# Ethernet.net
KiCad netlist of a schematic drawn in Altium Designer
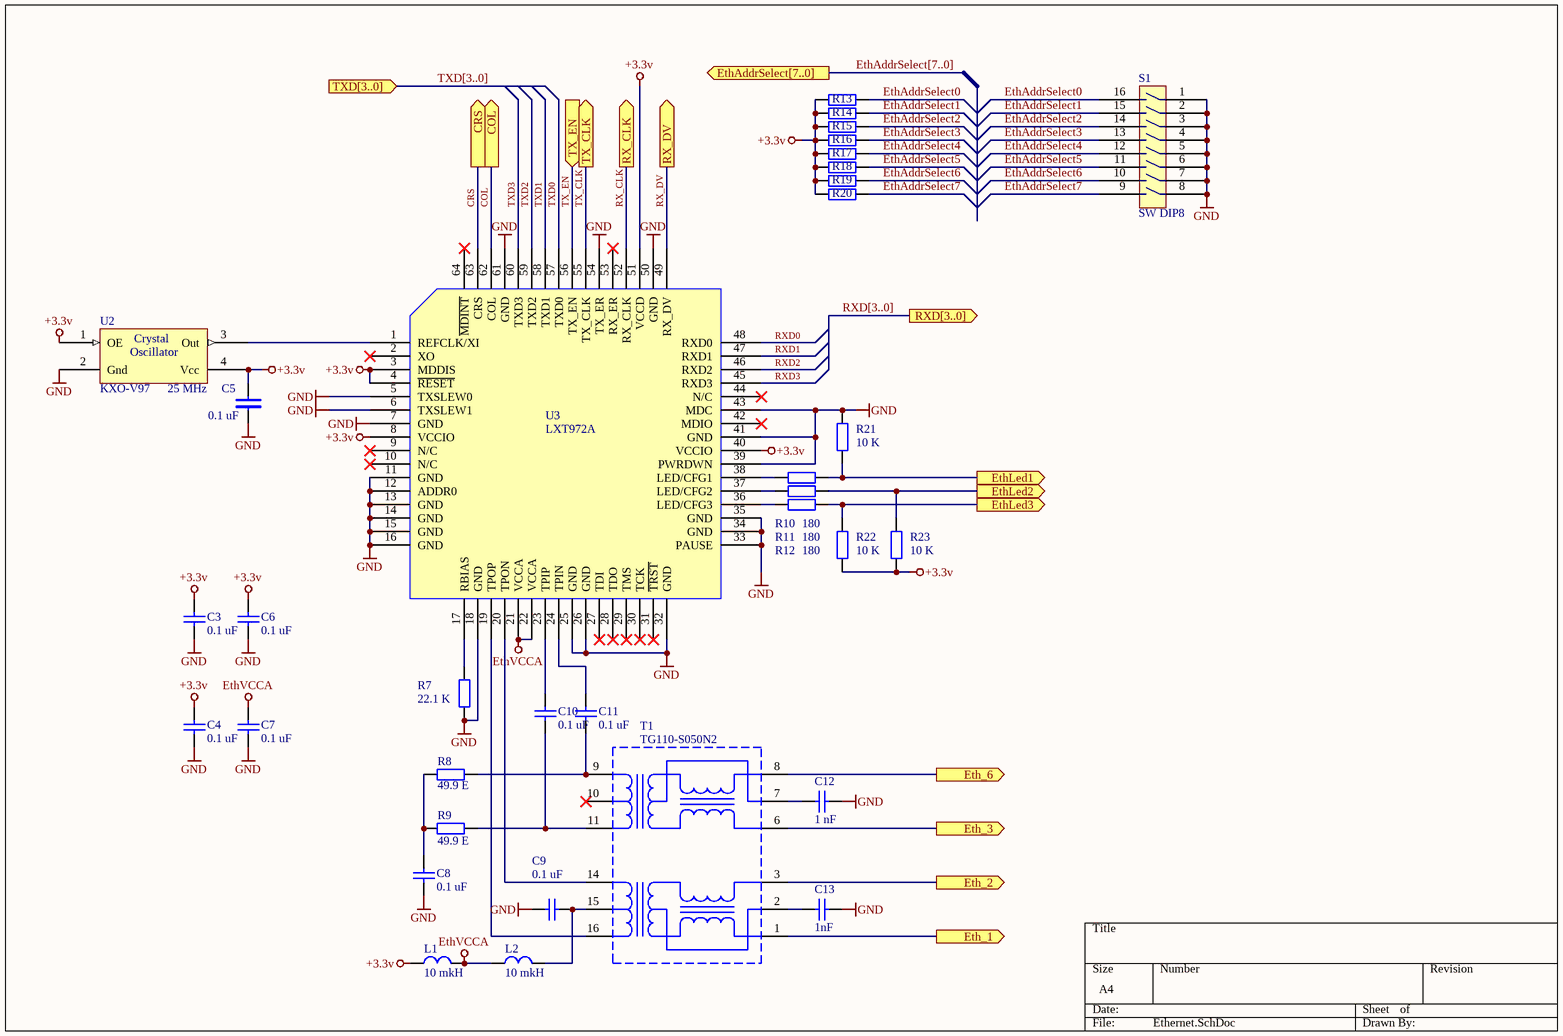
[diagram p0: Ethernet.SchDoc]

(export (version "E")
  (design (tool "Eeschema 10.0.6"))
  (components
    (comp (ref "C3")
      (value "0.1 uF")
      (footprint "0603")
      (description "Capacitor")
      (fields (field (name "PUBLISHER") "Altium Limited"))
      (libsource (lib "pcblib1") (part "Cap"))
    )
    (comp (ref "C4")
      (value "0.1 uF")
      (footprint "0603")
      (description "Capacitor")
      (fields (field (name "PUBLISHER") "Altium Limited"))
      (libsource (lib "pcblib1") (part "Cap"))
    )
    (comp (ref "C5") (value "0.1 uF") (footprint "1206") (libsource (lib "*") (part "C")))
    (comp (ref "C6")
      (value "0.1 uF")
      (footprint "0603")
      (description "Capacitor")
      (fields (field (name "PUBLISHER") "Altium Limited"))
      (libsource (lib "pcblib1") (part "Cap"))
    )
    (comp (ref "C7")
      (value "0.1 uF")
      (footprint "0603")
      (description "Capacitor")
      (fields (field (name "PUBLISHER") "Altium Limited"))
      (libsource (lib "pcblib1") (part "Cap"))
    )
    (comp (ref "C8")
      (value "0.1 uF")
      (footprint "0603")
      (description "Capacitor")
      (fields (field (name "PUBLISHER") "Altium Limited"))
      (libsource (lib "pcblib1") (part "Cap"))
    )
    (comp (ref "C9")
      (value "0.1 uF")
      (footprint "0603")
      (description "Capacitor")
      (fields (field (name "PUBLISHER") "Altium Limited"))
      (libsource (lib "pcblib1") (part "Cap"))
    )
    (comp (ref "C10")
      (value "0.1 uF")
      (footprint "0603")
      (description "Capacitor")
      (fields (field (name "PUBLISHER") "Altium Limited"))
      (libsource (lib "pcblib1") (part "Cap"))
    )
    (comp (ref "C11")
      (value "0.1 uF")
      (footprint "0603")
      (description "Capacitor")
      (fields (field (name "PUBLISHER") "Altium Limited"))
      (libsource (lib "pcblib1") (part "Cap"))
    )
    (comp (ref "C12")
      (value "1 nF")
      (footprint "1206")
      (description "Capacitor")
      (fields (field (name "PUBLISHER") "Altium Limited"))
      (libsource (lib "pcblib1") (part "Cap"))
    )
    (comp (ref "C13")
      (value "1nF")
      (footprint "1206")
      (description "Capacitor")
      (fields (field (name "Comment") "1 nF") (field (name "PUBLISHER") "Altium Limited"))
      (libsource (lib "pcblib1") (part "Cap"))
    )
    (comp (ref "L1")
      (value "10 mkH")
      (footprint "0805")
      (description "Inductor")
      (fields (field (name "PUBLISHER") "Altium Limited"))
      (libsource (lib "pcblib1") (part "Inductor"))
    )
    (comp (ref "L2")
      (value "10 mkH")
      (footprint "0805")
      (description "Inductor")
      (fields (field (name "PUBLISHER") "Altium Limited"))
      (libsource (lib "pcblib1") (part "Inductor"))
    )
    (comp (ref "R7")
      (value "22.1 K")
      (footprint "0805")
      (description "Resistor")
      (fields (field (name "PUBLISHER") "Altium Limited"))
      (libsource (lib "") (part "Res2_3"))
    )
    (comp (ref "R8")
      (value "49.9 E")
      (footprint "0805")
      (description "Resistor")
      (fields (field (name "PUBLISHER") "Altium Limited"))
      (libsource (lib "") (part "Res2_1"))
    )
    (comp (ref "R9")
      (value "49.9 E")
      (footprint "0805")
      (description "Resistor")
      (fields (field (name "PUBLISHER") "Altium Limited"))
      (libsource (lib "OD3M") (part "Res2"))
    )
    (comp (ref "R10")
      (value "180")
      (footprint "0805")
      (description "Resistor")
      (fields (field (name "PUBLISHER") "Altium Limited"))
      (libsource (lib "") (part "Res2_1"))
    )
    (comp (ref "R11")
      (value "180")
      (footprint "0805")
      (description "Resistor")
      (fields (field (name "PUBLISHER") "Altium Limited"))
      (libsource (lib "") (part "Res2_1"))
    )
    (comp (ref "R12")
      (value "180")
      (footprint "0805")
      (description "Resistor")
      (fields (field (name "PUBLISHER") "Altium Limited"))
      (libsource (lib "") (part "Res2_1"))
    )
    (comp (ref "R13")
      (value "10 K")
      (footprint "0603")
      (description "Resistor")
      (fields (field (name "PUBLISHER") "Altium Limited"))
      (libsource (lib "OD3M") (part "Res2"))
    )
    (comp (ref "R14")
      (value "10 K")
      (footprint "0603")
      (description "Resistor")
      (fields (field (name "PUBLISHER") "Altium Limited"))
      (libsource (lib "OD3M") (part "Res2"))
    )
    (comp (ref "R15")
      (value "10 K")
      (footprint "0603")
      (description "Resistor")
      (fields (field (name "PUBLISHER") "Altium Limited"))
      (libsource (lib "OD3M") (part "Res2"))
    )
    (comp (ref "R16")
      (value "10 K")
      (footprint "0603")
      (description "Resistor")
      (fields (field (name "PUBLISHER") "Altium Limited"))
      (libsource (lib "OD3M") (part "Res2"))
    )
    (comp (ref "R17")
      (value "10 K")
      (footprint "0603")
      (description "Resistor")
      (fields (field (name "PUBLISHER") "Altium Limited"))
      (libsource (lib "OD3M") (part "Res2"))
    )
    (comp (ref "R18")
      (value "10 K")
      (footprint "0603")
      (description "Resistor")
      (fields (field (name "PUBLISHER") "Altium Limited"))
      (libsource (lib "OD3M") (part "Res2"))
    )
    (comp (ref "R19")
      (value "10 K")
      (footprint "0603")
      (description "Resistor")
      (fields (field (name "PUBLISHER") "Altium Limited"))
      (libsource (lib "OD3M") (part "Res2"))
    )
    (comp (ref "R20")
      (value "10 K")
      (footprint "0603")
      (description "Resistor")
      (fields (field (name "PUBLISHER") "Altium Limited"))
      (libsource (lib "OD3M") (part "Res2"))
    )
    (comp (ref "R21")
      (value "10 K")
      (footprint "0603")
      (description "Resistor")
      (fields (field (name "PUBLISHER") "Altium Limited"))
      (libsource (lib "") (part "Res2_2"))
    )
    (comp (ref "R22")
      (value "10 K")
      (footprint "0603")
      (description "Resistor")
      (fields (field (name "PUBLISHER") "Altium Limited"))
      (libsource (lib "") (part "Res2_2"))
    )
    (comp (ref "R23")
      (value "10 K")
      (footprint "0603")
      (description "Resistor")
      (fields (field (name "PUBLISHER") "Altium Limited"))
      (libsource (lib "") (part "Res2_2"))
    )
    (comp (ref "S1") (value "SW DIP8") (footprint "SWD1-8") (libsource (lib "Adevice") (part "SW DIP8")))
    (comp (ref "T1")
      (value "TG110-S050N2")
      (footprint "SO-G16/G6.9")
      (libsource (lib "Schlib1") (part "TG110-S050N2"))
    )
    (comp (ref "U2")
      (value "KXO-V97")
      (footprint "KXO-97")
      (description "Crystal Oscillator (SMD)")
      (libsource (lib "Mylib") (part "SG-636"))
    )
    (comp (ref "U3")
      (value "LXT972A")
      (footprint "TQFP64")
      (libsource (lib "MyIntegratedLibrary") (part "LXT972A"))
    )
  )
  (nets
    (net (code "1") (name "+3.3v") (class "Default")
      (node (ref "C3") (pin "2") (pinfunction "2_2") (pintype "passive"))
      (node (ref "C4") (pin "2") (pinfunction "2_2") (pintype "passive"))
      (node (ref "C5") (pin "2") (pinfunction "2_2") (pintype "passive"))
      (node (ref "C6") (pin "2") (pinfunction "2_2") (pintype "passive"))
      (node (ref "L1") (pin "1") (pinfunction "1_1") (pintype "passive"))
      (node (ref "R13") (pin "2") (pinfunction "2_2") (pintype "passive"))
      (node (ref "R14") (pin "2") (pinfunction "2_2") (pintype "passive"))
      (node (ref "R15") (pin "2") (pinfunction "2_2") (pintype "passive"))
      (node (ref "R16") (pin "2") (pinfunction "2_2") (pintype "passive"))
      (node (ref "R17") (pin "2") (pinfunction "2_2") (pintype "passive"))
      (node (ref "R18") (pin "2") (pinfunction "2_2") (pintype "passive"))
      (node (ref "R19") (pin "2") (pinfunction "2_2") (pintype "passive"))
      (node (ref "R20") (pin "2") (pinfunction "2_2") (pintype "passive"))
      (node (ref "R22") (pin "1") (pinfunction "1_1") (pintype "passive"))
      (node (ref "R23") (pin "1") (pinfunction "1_1") (pintype "passive"))
      (node (ref "U2") (pin "1") (pinfunction "OE_1") (pintype "input"))
      (node (ref "U2") (pin "4") (pinfunction "Vcc_4") (pintype "passive"))
      (node (ref "U3") (pin "3") (pinfunction "MDDIS_3") (pintype "passive"))
      (node (ref "U3") (pin "4") (pinfunction "RESET_4") (pintype "passive"))
      (node (ref "U3") (pin "40") (pinfunction "VCCIO_40") (pintype "passive"))
      (node (ref "U3") (pin "51") (pinfunction "VCCD_51") (pintype "passive"))
      (node (ref "U3") (pin "8") (pinfunction "VCCIO_8") (pintype "passive"))
    )
    (net (code "2") (name "/COL") (class "Default")
      (node (ref "U3") (pin "62") (pinfunction "COL_62") (pintype "passive"))
    )
    (net (code "3") (name "/CRS") (class "Default")
      (node (ref "U3") (pin "63") (pinfunction "CRS_63") (pintype "passive"))
    )
    (net (code "4") (name "/EthAddrSelect0") (class "Default")
      (node (ref "R13") (pin "1") (pinfunction "1_1") (pintype "passive"))
      (node (ref "S1") (pin "16") (pinfunction "16_16") (pintype "passive"))
    )
    (net (code "5") (name "/EthAddrSelect1") (class "Default")
      (node (ref "R14") (pin "1") (pinfunction "1_1") (pintype "passive"))
      (node (ref "S1") (pin "15") (pinfunction "15_15") (pintype "passive"))
    )
    (net (code "6") (name "/EthAddrSelect2") (class "Default")
      (node (ref "R15") (pin "1") (pinfunction "1_1") (pintype "passive"))
      (node (ref "S1") (pin "14") (pinfunction "14_14") (pintype "passive"))
    )
    (net (code "7") (name "/EthAddrSelect3") (class "Default")
      (node (ref "R16") (pin "1") (pinfunction "1_1") (pintype "passive"))
      (node (ref "S1") (pin "13") (pinfunction "13_13") (pintype "passive"))
    )
    (net (code "8") (name "/EthAddrSelect4") (class "Default")
      (node (ref "R17") (pin "1") (pinfunction "1_1") (pintype "passive"))
      (node (ref "S1") (pin "12") (pinfunction "12_12") (pintype "passive"))
    )
    (net (code "9") (name "/EthAddrSelect5") (class "Default")
      (node (ref "R18") (pin "1") (pinfunction "1_1") (pintype "passive"))
      (node (ref "S1") (pin "11") (pinfunction "11_11") (pintype "passive"))
    )
    (net (code "10") (name "/EthAddrSelect6") (class "Default")
      (node (ref "R19") (pin "1") (pinfunction "1_1") (pintype "passive"))
      (node (ref "S1") (pin "10") (pinfunction "10_10") (pintype "passive"))
    )
    (net (code "11") (name "/EthAddrSelect7") (class "Default")
      (node (ref "R20") (pin "1") (pinfunction "1_1") (pintype "passive"))
      (node (ref "S1") (pin "9") (pinfunction "9_9") (pintype "passive"))
    )
    (net (code "13") (name "/EthLed1") (class "Default")
      (node (ref "R10") (pin "2") (pinfunction "2_2") (pintype "passive"))
      (node (ref "R21") (pin "1") (pinfunction "1_1") (pintype "passive"))
    )
    (net (code "14") (name "/EthLed2") (class "Default")
      (node (ref "R11") (pin "2") (pinfunction "2_2") (pintype "passive"))
      (node (ref "R23") (pin "2") (pinfunction "2_2") (pintype "passive"))
    )
    (net (code "15") (name "/EthLed3") (class "Default")
      (node (ref "R12") (pin "2") (pinfunction "2_2") (pintype "passive"))
      (node (ref "R22") (pin "2") (pinfunction "2_2") (pintype "passive"))
    )
    (net (code "16") (name "/Eth_1") (class "Default") (node (ref "T1") (pin "1") (pintype "passive")))
    (net (code "17") (name "/Eth_2") (class "Default") (node (ref "T1") (pin "3") (pintype "passive")))
    (net (code "18") (name "/Eth_3") (class "Default") (node (ref "T1") (pin "6") (pintype "passive")))
    (net (code "19") (name "/Eth_6") (class "Default") (node (ref "T1") (pin "8") (pintype "passive")))
    (net (code "20") (name "/RXD0") (class "Default")
      (node (ref "U3") (pin "48") (pinfunction "RXD0_48") (pintype "passive"))
    )
    (net (code "21") (name "/RXD1") (class "Default")
      (node (ref "U3") (pin "47") (pinfunction "RXD1_47") (pintype "passive"))
    )
    (net (code "22") (name "/RXD2") (class "Default")
      (node (ref "U3") (pin "46") (pinfunction "RXD2_46") (pintype "passive"))
    )
    (net (code "23") (name "/RXD3") (class "Default")
      (node (ref "U3") (pin "45") (pinfunction "RXD3_45") (pintype "passive"))
    )
    (net (code "25") (name "/RX_CLK") (class "Default")
      (node (ref "U3") (pin "52") (pinfunction "RX_CLK_52") (pintype "passive"))
    )
    (net (code "26") (name "/RX_DV") (class "Default")
      (node (ref "U3") (pin "49") (pinfunction "RX_DV_49") (pintype "passive"))
    )
    (net (code "27") (name "/TXD0") (class "Default")
      (node (ref "U3") (pin "57") (pinfunction "TXD0_57") (pintype "passive"))
    )
    (net (code "28") (name "/TXD1") (class "Default")
      (node (ref "U3") (pin "58") (pinfunction "TXD1_58") (pintype "passive"))
    )
    (net (code "29") (name "/TXD2") (class "Default")
      (node (ref "U3") (pin "59") (pinfunction "TXD2_59") (pintype "passive"))
    )
    (net (code "30") (name "/TXD3") (class "Default")
      (node (ref "U3") (pin "60") (pinfunction "TXD3_60") (pintype "passive"))
    )
    (net (code "32") (name "/TX_CLK") (class "Default")
      (node (ref "U3") (pin "55") (pinfunction "TX_CLK_55") (pintype "passive"))
    )
    (net (code "33") (name "/TX_EN") (class "Default")
      (node (ref "U3") (pin "56") (pinfunction "TX_EN_56") (pintype "passive"))
    )
    (net (code "34") (name "EthVCCA") (class "Default")
      (node (ref "C7") (pin "2") (pinfunction "2_2") (pintype "passive"))
      (node (ref "L1") (pin "2") (pinfunction "2_2") (pintype "passive"))
      (node (ref "L2") (pin "1") (pinfunction "1_1") (pintype "passive"))
      (node (ref "U3") (pin "21") (pinfunction "VCCA_21") (pintype "passive"))
      (node (ref "U3") (pin "22") (pinfunction "VCCA_22") (pintype "passive"))
    )
    (net (code "35") (name "GND") (class "Default")
      (node (ref "C12") (pin "2") (pinfunction "2_2") (pintype "passive"))
      (node (ref "C13") (pin "1") (pinfunction "1_1") (pintype "passive"))
      (node (ref "C3") (pin "1") (pinfunction "1_1") (pintype "passive"))
      (node (ref "C4") (pin "1") (pinfunction "1_1") (pintype "passive"))
      (node (ref "C5") (pin "1") (pinfunction "1_1") (pintype "passive"))
      (node (ref "C6") (pin "1") (pinfunction "1_1") (pintype "passive"))
      (node (ref "C7") (pin "1") (pinfunction "1_1") (pintype "passive"))
      (node (ref "C8") (pin "2") (pinfunction "2_2") (pintype "passive"))
      (node (ref "C9") (pin "1") (pinfunction "1_1") (pintype "passive"))
      (node (ref "R21") (pin "2") (pinfunction "2_2") (pintype "passive"))
      (node (ref "R7") (pin "2") (pinfunction "2_2") (pintype "passive"))
      (node (ref "S1") (pin "1") (pinfunction "1_1") (pintype "passive"))
      (node (ref "S1") (pin "2") (pinfunction "2_2") (pintype "passive"))
      (node (ref "S1") (pin "3") (pinfunction "3_3") (pintype "passive"))
      (node (ref "S1") (pin "4") (pinfunction "4_4") (pintype "passive"))
      (node (ref "S1") (pin "5") (pinfunction "5_5") (pintype "passive"))
      (node (ref "S1") (pin "6") (pinfunction "6_6") (pintype "passive"))
      (node (ref "S1") (pin "7") (pinfunction "7_7") (pintype "passive"))
      (node (ref "S1") (pin "8") (pinfunction "8_8") (pintype "passive"))
      (node (ref "U2") (pin "2") (pinfunction "Gnd_2") (pintype "power_in"))
      (node (ref "U3") (pin "11") (pinfunction "GND_11") (pintype "passive"))
      (node (ref "U3") (pin "12") (pinfunction "ADDR0_12") (pintype "passive"))
      (node (ref "U3") (pin "13") (pinfunction "GND_13") (pintype "passive"))
      (node (ref "U3") (pin "14") (pinfunction "GND_14") (pintype "passive"))
      (node (ref "U3") (pin "15") (pinfunction "GND_15") (pintype "passive"))
      (node (ref "U3") (pin "16") (pinfunction "GND_16") (pintype "passive"))
      (node (ref "U3") (pin "18") (pinfunction "GND_18") (pintype "passive"))
      (node (ref "U3") (pin "25") (pinfunction "GND_25") (pintype "passive"))
      (node (ref "U3") (pin "26") (pinfunction "GND_26") (pintype "passive"))
      (node (ref "U3") (pin "32") (pinfunction "GND_32") (pintype "passive"))
      (node (ref "U3") (pin "33") (pinfunction "PAUSE_33") (pintype "passive"))
      (node (ref "U3") (pin "34") (pinfunction "GND_34") (pintype "passive"))
      (node (ref "U3") (pin "35") (pinfunction "GND_35") (pintype "passive"))
      (node (ref "U3") (pin "39") (pinfunction "PWRDWN_39") (pintype "passive"))
      (node (ref "U3") (pin "41") (pinfunction "GND_41") (pintype "passive"))
      (node (ref "U3") (pin "43") (pinfunction "MDC_43") (pintype "passive"))
      (node (ref "U3") (pin "5") (pinfunction "TXSLEW0_5") (pintype "passive"))
      (node (ref "U3") (pin "50") (pinfunction "GND_50") (pintype "passive"))
      (node (ref "U3") (pin "54") (pinfunction "TX_ER_54") (pintype "passive"))
      (node (ref "U3") (pin "6") (pinfunction "TXSLEW1_6") (pintype "passive"))
      (node (ref "U3") (pin "61") (pinfunction "GND_61") (pintype "passive"))
      (node (ref "U3") (pin "7") (pinfunction "GND_7") (pintype "passive"))
    )
    (net (code "36") (name "Net-(C8-Pad1)") (class "Default")
      (node (ref "C8") (pin "1") (pinfunction "1_1") (pintype "passive"))
      (node (ref "R8") (pin "1") (pinfunction "1_1") (pintype "passive"))
      (node (ref "R9") (pin "2") (pinfunction "2_2") (pintype "passive"))
    )
    (net (code "37") (name "Net-(C9-Pad2)") (class "Default")
      (node (ref "C9") (pin "2") (pinfunction "2_2") (pintype "passive"))
      (node (ref "L2") (pin "2") (pinfunction "2_2") (pintype "passive"))
      (node (ref "T1") (pin "15") (pintype "passive"))
    )
    (net (code "38") (name "Net-(C10-Pad1)") (class "Default")
      (node (ref "C10") (pin "1") (pinfunction "1_1") (pintype "passive"))
      (node (ref "R9") (pin "1") (pinfunction "1_1") (pintype "passive"))
      (node (ref "T1") (pin "11") (pintype "passive"))
    )
    (net (code "39") (name "Net-(C11-Pad1)") (class "Default")
      (node (ref "C11") (pin "1") (pinfunction "1_1") (pintype "passive"))
      (node (ref "R8") (pin "2") (pinfunction "2_2") (pintype "passive"))
      (node (ref "T1") (pin "9") (pintype "passive"))
    )
    (net (code "40") (name "Net-(C12-Pad1)") (class "Default")
      (node (ref "C12") (pin "1") (pinfunction "1_1") (pintype "passive"))
      (node (ref "T1") (pin "7") (pintype "passive"))
    )
    (net (code "41") (name "Net-(C13-Pad2)") (class "Default")
      (node (ref "C13") (pin "2") (pinfunction "2_2") (pintype "passive"))
      (node (ref "T1") (pin "2") (pintype "passive"))
    )
    (net (code "42") (name "Net-(U2-Out)") (class "Default")
      (node (ref "U2") (pin "3") (pinfunction "Out_3") (pintype "output"))
      (node (ref "U3") (pin "1") (pinfunction "REFCLK/XI_1") (pintype "passive"))
    )
    (net (code "43") (name "Net-(U3-LED{slash}CFG1)") (class "Default")
      (node (ref "R10") (pin "1") (pinfunction "1_1") (pintype "passive"))
      (node (ref "U3") (pin "38") (pinfunction "LED/CFG1_38") (pintype "passive"))
    )
    (net (code "44") (name "Net-(U3-LED{slash}CFG2)") (class "Default")
      (node (ref "R11") (pin "1") (pinfunction "1_1") (pintype "passive"))
      (node (ref "U3") (pin "37") (pinfunction "LED/CFG2_37") (pintype "passive"))
    )
    (net (code "45") (name "Net-(U3-LED{slash}CFG3)") (class "Default")
      (node (ref "R12") (pin "1") (pinfunction "1_1") (pintype "passive"))
      (node (ref "U3") (pin "36") (pinfunction "LED/CFG3_36") (pintype "passive"))
    )
    (net (code "46") (name "Net-(U3-RBIAS)") (class "Default")
      (node (ref "R7") (pin "1") (pinfunction "1_1") (pintype "passive"))
      (node (ref "U3") (pin "17") (pinfunction "RBIAS_17") (pintype "passive"))
    )
    (net (code "47") (name "Net-(U3-TPIN)") (class "Default")
      (node (ref "C11") (pin "2") (pinfunction "2_2") (pintype "passive"))
      (node (ref "U3") (pin "24") (pinfunction "TPIN_24") (pintype "passive"))
    )
    (net (code "48") (name "Net-(U3-TPIP)") (class "Default")
      (node (ref "C10") (pin "2") (pinfunction "2_2") (pintype "passive"))
      (node (ref "U3") (pin "23") (pinfunction "TPIP_23") (pintype "passive"))
    )
    (net (code "49") (name "Net-(U3-TPON)") (class "Default")
      (node (ref "T1") (pin "14") (pintype "passive"))
      (node (ref "U3") (pin "20") (pinfunction "TPON_20") (pintype "passive"))
    )
    (net (code "50") (name "Net-(U3-TPOP)") (class "Default")
      (node (ref "T1") (pin "16") (pintype "passive"))
      (node (ref "U3") (pin "19") (pinfunction "TPOP_19") (pintype "passive"))
    )
    (net (code "51") (name "unconnected-(T1-Pad10)") (class "Default")
      (node (ref "T1") (pin "10") (pintype "passive+no_connect"))
    )
    (net (code "52") (name "unconnected-(U3-MDINT-Pad64)") (class "Default")
      (node (ref "U3") (pin "64") (pinfunction "MDINT_64") (pintype "passive+no_connect"))
    )
    (net (code "53") (name "unconnected-(U3-MDIO-Pad42)") (class "Default")
      (node (ref "U3") (pin "42") (pinfunction "MDIO_42") (pintype "passive+no_connect"))
    )
    (net (code "54") (name "unconnected-(U3-N{slash}C-Pad9)") (class "Default")
      (node (ref "U3") (pin "9") (pinfunction "N/C_9") (pintype "passive+no_connect"))
    )
    (net (code "55") (name "unconnected-(U3-N{slash}C-Pad10)") (class "Default")
      (node (ref "U3") (pin "10") (pinfunction "N/C_10") (pintype "passive+no_connect"))
    )
    (net (code "56") (name "unconnected-(U3-N{slash}C-Pad44)") (class "Default")
      (node (ref "U3") (pin "44") (pinfunction "N/C_44") (pintype "passive+no_connect"))
    )
    (net (code "57") (name "unconnected-(U3-RX_ER-Pad53)") (class "Default")
      (node (ref "U3") (pin "53") (pinfunction "RX_ER_53") (pintype "passive+no_connect"))
    )
    (net (code "58") (name "unconnected-(U3-TCK-Pad30)") (class "Default")
      (node (ref "U3") (pin "30") (pinfunction "TCK_30") (pintype "passive+no_connect"))
    )
    (net (code "59") (name "unconnected-(U3-TDI-Pad27)") (class "Default")
      (node (ref "U3") (pin "27") (pinfunction "TDI_27") (pintype "passive+no_connect"))
    )
    (net (code "60") (name "unconnected-(U3-TDO-Pad28)") (class "Default")
      (node (ref "U3") (pin "28") (pinfunction "TDO_28") (pintype "passive+no_connect"))
    )
    (net (code "61") (name "unconnected-(U3-TMS-Pad29)") (class "Default")
      (node (ref "U3") (pin "29") (pinfunction "TMS_29") (pintype "passive+no_connect"))
    )
    (net (code "62") (name "unconnected-(U3-TRST-Pad31)") (class "Default")
      (node (ref "U3") (pin "31") (pinfunction "TRST_31") (pintype "passive+no_connect"))
    )
    (net (code "63") (name "unconnected-(U3-XO-Pad2)") (class "Default")
      (node (ref "U3") (pin "2") (pinfunction "XO_2") (pintype "passive+no_connect"))
    )
  )
)
